# FRA_daughter_v1.net
KiCad netlist of a schematic drawn in EAGLE
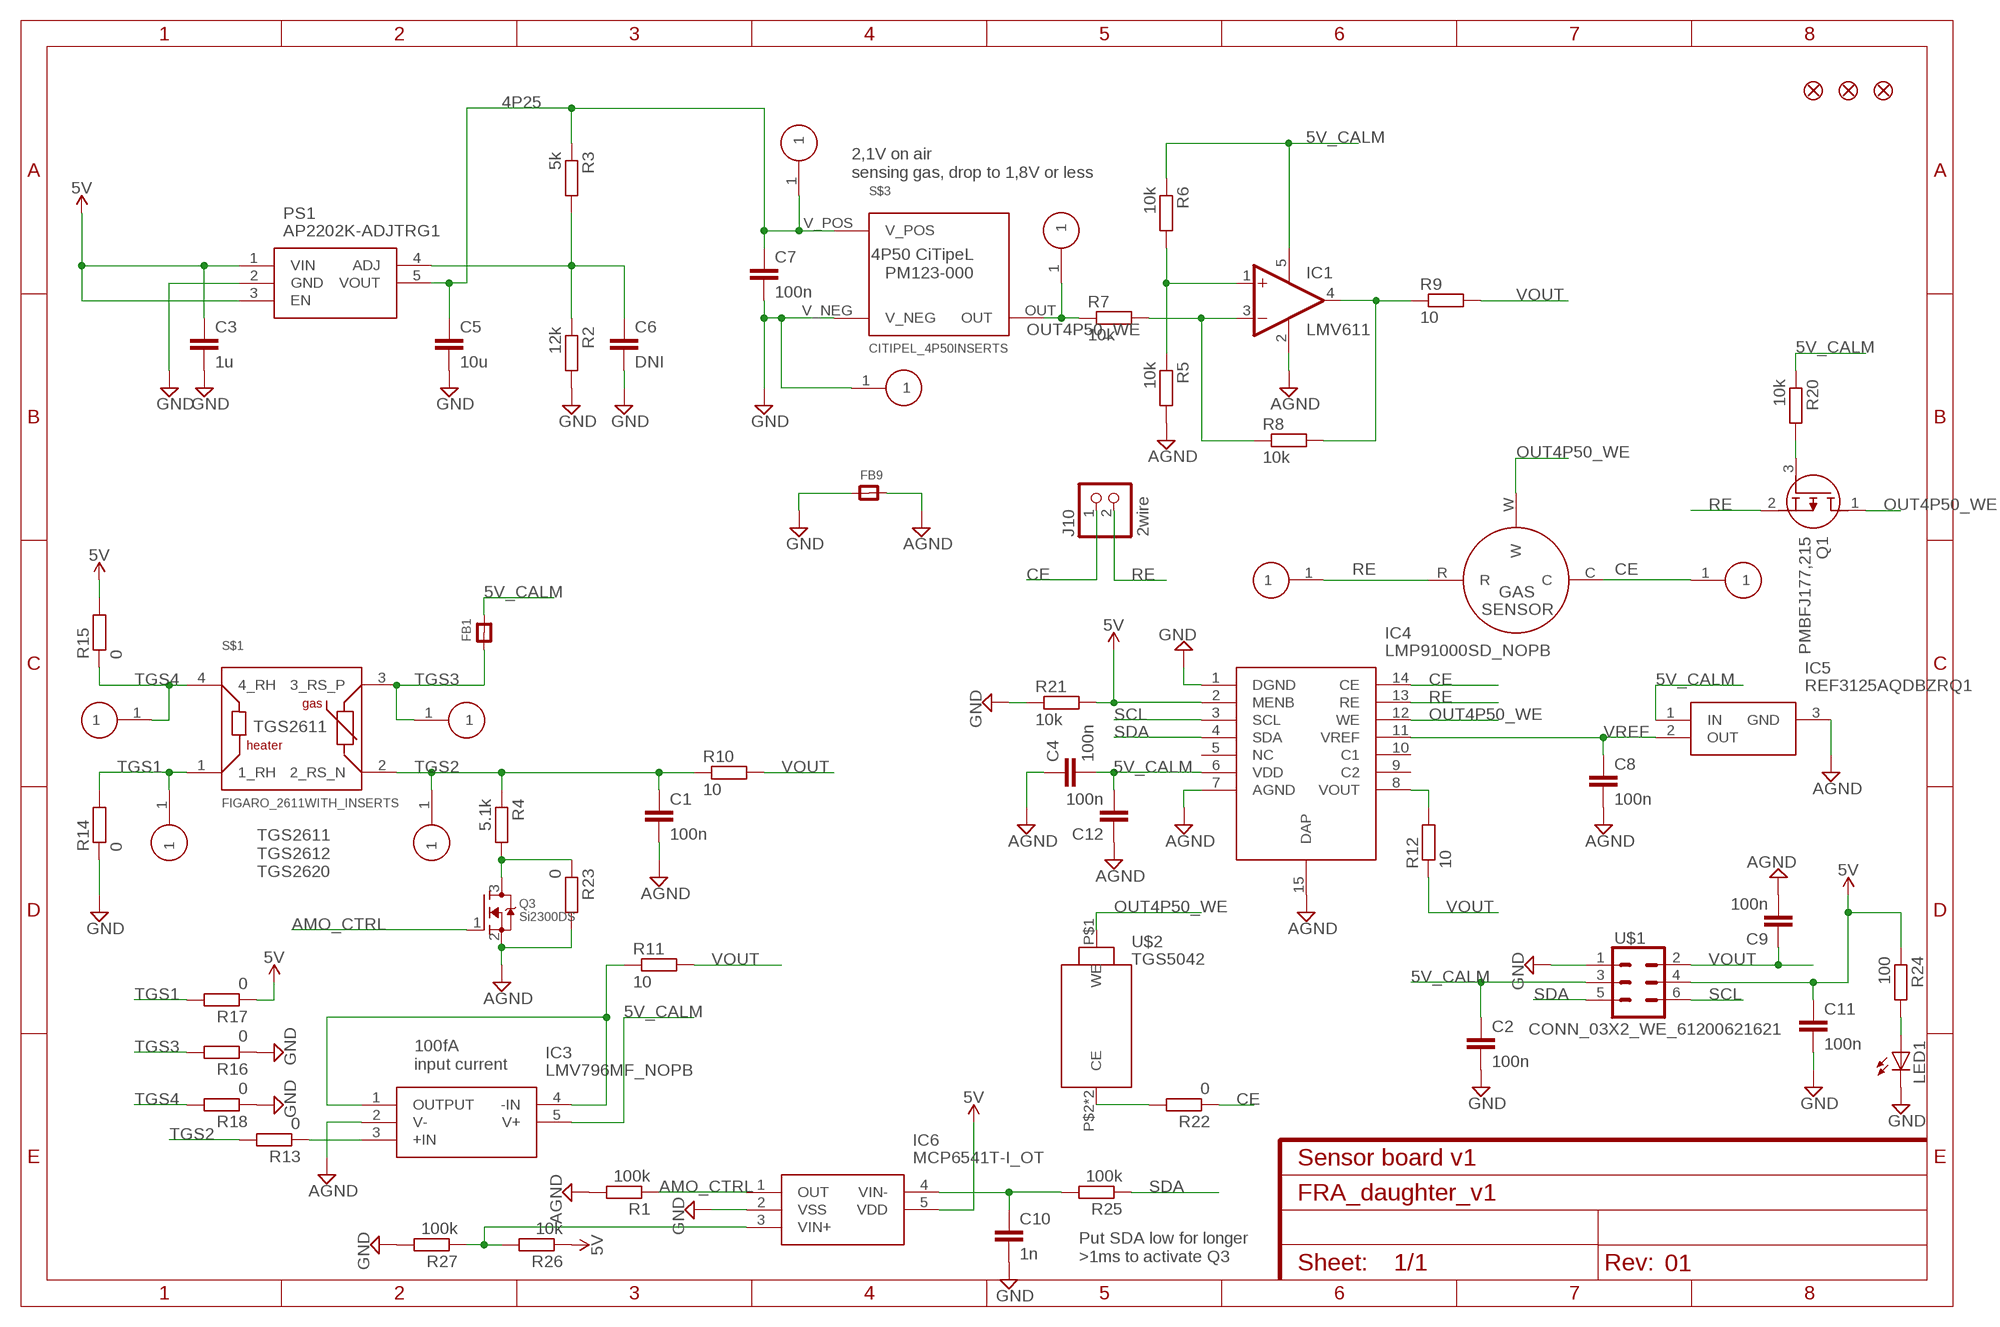
[diagram p0: schematic, sheet 1]

(export (version "E")
  (design (tool "Eeschema 10.0.6"))
  (components
    (comp (ref "C1")
      (value "100n")
      (footprint "eagle-import:C0603K")
      (libsource (lib "eagle-import") (part "C-EUC0603K"))
    )
    (comp (ref "C2")
      (value "100n")
      (footprint "eagle-import:C0603K")
      (libsource (lib "eagle-import") (part "C-EUC0603K"))
    )
    (comp (ref "C3")
      (value "1u")
      (footprint "eagle-import:C0603K")
      (libsource (lib "eagle-import") (part "C-EUC0603K"))
    )
    (comp (ref "C4")
      (value "100n")
      (footprint "eagle-import:C0603K")
      (libsource (lib "eagle-import") (part "C-EUC0603K"))
    )
    (comp (ref "C5")
      (value "10u")
      (footprint "eagle-import:C0603K")
      (libsource (lib "eagle-import") (part "C-EUC0603K"))
    )
    (comp (ref "C6")
      (value "DNI")
      (footprint "eagle-import:C0603K")
      (libsource (lib "eagle-import") (part "C-EUC0603K"))
    )
    (comp (ref "C7")
      (value "100n")
      (footprint "eagle-import:C0603K")
      (libsource (lib "eagle-import") (part "C-EUC0603K"))
    )
    (comp (ref "C8")
      (value "100n")
      (footprint "eagle-import:C0603K")
      (libsource (lib "eagle-import") (part "C-EUC0603K"))
    )
    (comp (ref "C9")
      (value "100n")
      (footprint "eagle-import:C0603K")
      (libsource (lib "eagle-import") (part "C-EUC0603K"))
    )
    (comp (ref "C10")
      (value "1n")
      (footprint "eagle-import:C0603K")
      (libsource (lib "eagle-import") (part "C-EUC0603K"))
    )
    (comp (ref "C11")
      (value "100n")
      (footprint "eagle-import:C0603K")
      (libsource (lib "eagle-import") (part "C-EUC0603K"))
    )
    (comp (ref "C12")
      (value "100n")
      (footprint "eagle-import:C0603K")
      (libsource (lib "eagle-import") (part "C-EUC0603K"))
    )
    (comp (ref "FB1")
      (value "FERRITE")
      (footprint "eagle-import:0603")
      (fields (field (name "PARTNO") "BLM18PG121SN1D"))
      (libsource (lib "eagle-import") (part "FERRITE"))
    )
    (comp (ref "FB9")
      (value "FERRITE")
      (footprint "eagle-import:0603")
      (fields (field (name "PARTNO") "BLM18PG121SN1D"))
      (libsource (lib "eagle-import") (part "FERRITE"))
    )
    (comp (ref "FID1")
      (value "FIDUCIAL\"\"")
      (footprint "eagle-import:FIDUCIAL_1MM")
      (libsource (lib "eagle-import") (part "FIDUCIAL{dblquote}{dblquote}"))
    )
    (comp (ref "FID2")
      (value "FIDUCIAL\"\"")
      (footprint "eagle-import:FIDUCIAL_1MM")
      (libsource (lib "eagle-import") (part "FIDUCIAL{dblquote}{dblquote}"))
    )
    (comp (ref "FID4")
      (value "FIDUCIAL\"\"")
      (footprint "eagle-import:FIDUCIAL_1MM")
      (libsource (lib "eagle-import") (part "FIDUCIAL{dblquote}{dblquote}"))
    )
    (comp (ref "IC1")
      (value "LMV611")
      (footprint "eagle-import:SC70-5L")
      (libsource (lib "eagle-import") (part "OPA333DCK"))
    )
    (comp (ref "IC3")
      (value "LMV796MF_NOPB")
      (footprint "eagle-import:SOT95P280X145-5N")
      (fields
        (field (name "MANUFACTURER_PART_NUMBER") "LMV796MF/NOPB")
        (field (name "MOUSER_PART_NUMBER") "926-LMV796MF/NOPB")
      )
      (libsource (lib "eagle-import") (part "LMV796MF_NOPB"))
    )
    (comp (ref "IC4")
      (value "LMP91000SD_NOPB")
      (footprint "eagle-import:SON50P400X400X80-15N")
      (fields
        (field (name "MANUFACTURER_PART_NUMBER") "LMP91000SD/NOPB")
        (field (name "MOUSER_PART_NUMBER") "926-LMP91000SD/NOPB")
      )
      (libsource (lib "eagle-import") (part "LMP91000SD_NOPB"))
    )
    (comp (ref "IC5")
      (value "REF3125AQDBZRQ1")
      (footprint "eagle-import:SOT95P237X112-3N")
      (fields (field (name "MOUSER_PART_NUMBER") "595-REF3125AQDBZRQ1"))
      (libsource (lib "eagle-import") (part "REF3125AQDBZRQ1"))
    )
    (comp (ref "IC6")
      (value "MCP6541T-I_OT")
      (footprint "eagle-import:SOT95P270X145-5N")
      (fields
        (field (name "MANUFACTURER_PART_NUMBER") "MCP6541T-I/OT")
        (field (name "MOUSER_PART_NUMBER") "579-MCP6541T-I/OT")
      )
      (libsource (lib "eagle-import") (part "MCP6541T-I_OT"))
    )
    (comp (ref "J1")
      (value "INSERT_MM5_06691.5MM")
      (footprint "eagle-import:INSERT_1MM5_9372")
      (libsource (lib "eagle-import") (part "INSERT_MM5_06691.5MM"))
    )
    (comp (ref "J2")
      (value "TGS3")
      (footprint "eagle-import:INSERT_MM5_0669")
      (libsource (lib "eagle-import") (part "INSERT_MM5_0669"))
    )
    (comp (ref "J3")
      (value "TGS2")
      (footprint "eagle-import:INSERT_MM5_0669")
      (libsource (lib "eagle-import") (part "INSERT_MM5_0669"))
    )
    (comp (ref "J4")
      (value "TGS1")
      (footprint "eagle-import:INSERT_MM5_0669")
      (libsource (lib "eagle-import") (part "INSERT_MM5_0669"))
    )
    (comp (ref "J5")
      (value "TGS4")
      (footprint "eagle-import:INSERT_MM5_0669")
      (libsource (lib "eagle-import") (part "INSERT_MM5_0669"))
    )
    (comp (ref "J6")
      (value "INSERT_MM5_06691.5MM")
      (footprint "eagle-import:INSERT_1MM5_9372")
      (libsource (lib "eagle-import") (part "INSERT_MM5_06691.5MM"))
    )
    (comp (ref "J7")
      (value "INSERT_MM5_06691.5MM")
      (footprint "eagle-import:INSERT_1MM5_9372")
      (libsource (lib "eagle-import") (part "INSERT_MM5_06691.5MM"))
    )
    (comp (ref "J8")
      (value "INSERT_MM5_06691.5MM")
      (footprint "eagle-import:INSERT_1MM5_9372")
      (libsource (lib "eagle-import") (part "INSERT_MM5_06691.5MM"))
    )
    (comp (ref "J9")
      (value "INSERT_MM5_06691.5MM")
      (footprint "eagle-import:INSERT_1MM5_9372")
      (libsource (lib "eagle-import") (part "INSERT_MM5_06691.5MM"))
    )
    (comp (ref "J10")
      (value "2wire")
      (footprint "eagle-import:1X02")
      (fields (field (name "PARTNO") "TSW-102-07-G-S"))
      (libsource (lib "eagle-import") (part "PINHD-1X2"))
    )
    (comp (ref "LED1")
      (value "LEDCHIP-LED0603")
      (footprint "eagle-import:CHIP-LED0603")
      (libsource (lib "eagle-import") (part "LEDCHIP-LED0603"))
    )
    (comp (ref "PS1")
      (value "AP2202K-ADJTRG1")
      (footprint "eagle-import:SOT95P280X145-5N")
      (fields (field (name "MOUSER_PART_NUMBER") "621-AP2202K-ADJTRG1"))
      (libsource (lib "eagle-import") (part "AP2202K-ADJTRG1"))
    )
    (comp (ref "Q1")
      (value "PMBFJ177,215")
      (footprint "eagle-import:SOT95P230X110-3N")
      (fields (field (name "MOUSER_PART_NUMBER") "771-PMBFJ177-T/R"))
      (libsource (lib "eagle-import") (part "PMBFJ177,215"))
    )
    (comp (ref "Q3")
      (value "Si2300DS")
      (footprint "eagle-import:SOT23")
      (libsource (lib "eagle-import") (part "MOSFET-NREFLOW"))
    )
    (comp (ref "R1")
      (value "100k")
      (footprint "eagle-import:R0603")
      (libsource (lib "eagle-import") (part "R-EU_R0603"))
    )
    (comp (ref "R2")
      (value "12k")
      (footprint "eagle-import:R0603")
      (libsource (lib "eagle-import") (part "R-EU_R0603"))
    )
    (comp (ref "R3")
      (value "5k")
      (footprint "eagle-import:R0603")
      (libsource (lib "eagle-import") (part "R-EU_R0603"))
    )
    (comp (ref "R4")
      (value "5.1k")
      (footprint "eagle-import:R0603")
      (libsource (lib "eagle-import") (part "R-EU_R0603"))
    )
    (comp (ref "R5")
      (value "10k")
      (footprint "eagle-import:R0603")
      (libsource (lib "eagle-import") (part "R-EU_R0603"))
    )
    (comp (ref "R6")
      (value "10k")
      (footprint "eagle-import:R0603")
      (libsource (lib "eagle-import") (part "R-EU_R0603"))
    )
    (comp (ref "R7")
      (value "10k")
      (footprint "eagle-import:R0603")
      (libsource (lib "eagle-import") (part "R-EU_R0603"))
    )
    (comp (ref "R8")
      (value "10k")
      (footprint "eagle-import:R0603")
      (libsource (lib "eagle-import") (part "R-EU_R0603"))
    )
    (comp (ref "R9")
      (value "10")
      (footprint "eagle-import:R0603")
      (libsource (lib "eagle-import") (part "R-EU_R0603"))
    )
    (comp (ref "R10")
      (value "10")
      (footprint "eagle-import:R0603")
      (libsource (lib "eagle-import") (part "R-EU_R0603"))
    )
    (comp (ref "R11")
      (value "10")
      (footprint "eagle-import:R0603")
      (libsource (lib "eagle-import") (part "R-EU_R0603"))
    )
    (comp (ref "R12")
      (value "10")
      (footprint "eagle-import:R0603")
      (libsource (lib "eagle-import") (part "R-EU_R0603"))
    )
    (comp (ref "R13")
      (value "0")
      (footprint "eagle-import:R0603")
      (libsource (lib "eagle-import") (part "R-EU_R0603"))
    )
    (comp (ref "R14")
      (value "0")
      (footprint "eagle-import:R0603")
      (libsource (lib "eagle-import") (part "R-EU_R0603"))
    )
    (comp (ref "R15")
      (value "0")
      (footprint "eagle-import:R0603")
      (libsource (lib "eagle-import") (part "R-EU_R0603"))
    )
    (comp (ref "R16")
      (value "0")
      (footprint "eagle-import:R0603")
      (libsource (lib "eagle-import") (part "R-EU_R0603"))
    )
    (comp (ref "R17")
      (value "0")
      (footprint "eagle-import:R0603")
      (libsource (lib "eagle-import") (part "R-EU_R0603"))
    )
    (comp (ref "R18")
      (value "0")
      (footprint "eagle-import:R0603")
      (libsource (lib "eagle-import") (part "R-EU_R0603"))
    )
    (comp (ref "R20")
      (value "10k")
      (footprint "eagle-import:R0603")
      (libsource (lib "eagle-import") (part "R-EU_R0603"))
    )
    (comp (ref "R21")
      (value "10k")
      (footprint "eagle-import:R0603")
      (libsource (lib "eagle-import") (part "R-EU_R0603"))
    )
    (comp (ref "R22")
      (value "0")
      (footprint "eagle-import:R0603")
      (libsource (lib "eagle-import") (part "R-EU_R0603"))
    )
    (comp (ref "R23")
      (value "0")
      (footprint "eagle-import:R0603")
      (libsource (lib "eagle-import") (part "R-EU_R0603"))
    )
    (comp (ref "R24")
      (value "100")
      (footprint "eagle-import:R0603")
      (libsource (lib "eagle-import") (part "R-EU_R0603"))
    )
    (comp (ref "R25")
      (value "100k")
      (footprint "eagle-import:R0603")
      (libsource (lib "eagle-import") (part "R-EU_R0603"))
    )
    (comp (ref "R26")
      (value "10k")
      (footprint "eagle-import:R0603")
      (libsource (lib "eagle-import") (part "R-EU_R0603"))
    )
    (comp (ref "R27")
      (value "100k")
      (footprint "eagle-import:R0603")
      (libsource (lib "eagle-import") (part "R-EU_R0603"))
    )
    (comp (ref "S$1")
      (value "FIGARO_2611WITH_INSERTS")
      (footprint "eagle-import:TH4_TGS2611_INSERTS")
      (libsource (lib "eagle-import") (part "FIGARO_2611WITH_INSERTS"))
    )
    (comp (ref "S$3")
      (value "CITIPEL_4P50INSERTS")
      (footprint "eagle-import:TH3_4P50_INSERTS")
      (libsource (lib "eagle-import") (part "CITIPEL_4P50INSERTS"))
    )
    (comp (ref "U$1")
      (value "CONN_03X2_WE_61200621621")
      (footprint "eagle-import:WE_61200621621")
      (libsource (lib "eagle-import") (part "CONN_03X2_WE_61200621621"))
    )
    (comp (ref "U$2")
      (value "TGS5042")
      (footprint "eagle-import:TGS5042")
      (libsource (lib "eagle-import") (part "TGS5042"))
    )
    (comp (ref "X1")
      (value "3-ELECTRODE-GAS-SENSORINS")
      (footprint "eagle-import:3-ELECTRODE_INSETRS")
      (libsource (lib "eagle-import") (part "3-ELECTRODE-GAS-SENSORINS"))
    )
  )
  (nets
    (net (code "1") (name "/4P25") (class "Default")
      (node (ref "C5") (pin "1") (pinfunction "1_1") (pintype "passive"))
      (node (ref "C7") (pin "1") (pinfunction "1_1") (pintype "passive"))
      (node (ref "J6") (pin "1") (pinfunction "1_1") (pintype "bidirectional"))
      (node (ref "PS1") (pin "5") (pinfunction "VOUT_5") (pintype "power_in"))
      (node (ref "R3") (pin "1") (pinfunction "1_1") (pintype "passive"))
      (node (ref "S$3") (pin "V_POS") (pinfunction "V_POS_V_POS") (pintype "power_in"))
    )
    (net (code "2") (name "/5V_CALM") (class "Default")
      (node (ref "C12") (pin "2") (pinfunction "2_2") (pintype "passive"))
      (node (ref "C2") (pin "1") (pinfunction "1_1") (pintype "passive"))
      (node (ref "C4") (pin "2") (pinfunction "2_2") (pintype "passive"))
      (node (ref "FB1") (pin "2") (pinfunction "P$2_2") (pintype "passive"))
      (node (ref "IC1") (pin "5") (pinfunction "V+_5") (pintype "power_in"))
      (node (ref "IC3") (pin "5") (pinfunction "V+_5") (pintype "bidirectional"))
      (node (ref "IC4") (pin "6") (pinfunction "VDD_6") (pintype "power_in"))
      (node (ref "IC5") (pin "1") (pinfunction "IN_1") (pintype "bidirectional"))
      (node (ref "R20") (pin "1") (pinfunction "1_1") (pintype "passive"))
      (node (ref "R6") (pin "1") (pinfunction "1_1") (pintype "passive"))
      (node (ref "U$1") (pin "3") (pinfunction "3_3") (pintype "bidirectional"))
    )
    (net (code "3") (name "/AMO_CTRL") (class "Default")
      (node (ref "IC6") (pin "1") (pinfunction "OUT_1") (pintype "output"))
      (node (ref "Q3") (pin "1") (pinfunction "G_1") (pintype "bidirectional"))
      (node (ref "R1") (pin "1") (pinfunction "1_1") (pintype "passive"))
    )
    (net (code "4") (name "/CE") (class "Default")
      (node (ref "IC4") (pin "14") (pinfunction "CE_14") (pintype "input"))
      (node (ref "J10") (pin "1") (pinfunction "1_1") (pintype "passive"))
      (node (ref "J9") (pin "1") (pinfunction "1_1") (pintype "bidirectional"))
      (node (ref "R22") (pin "1") (pinfunction "1_1") (pintype "passive"))
      (node (ref "X1") (pin "C") (pinfunction "C_C") (pintype "bidirectional"))
    )
    (net (code "5") (name "/OUT4P50_WE") (class "Default")
      (node (ref "IC4") (pin "12") (pinfunction "WE_12") (pintype "input"))
      (node (ref "J7") (pin "1") (pinfunction "1_1") (pintype "bidirectional"))
      (node (ref "Q1") (pin "1") (pinfunction "D_1") (pintype "bidirectional"))
      (node (ref "R7") (pin "1") (pinfunction "1_1") (pintype "passive"))
      (node (ref "S$3") (pin "OUT") (pinfunction "OUT_OUT") (pintype "bidirectional"))
      (node (ref "U$2") (pin "P$1") (pinfunction "WE_P$1") (pintype "bidirectional"))
      (node (ref "X1") (pin "W") (pinfunction "W_W") (pintype "bidirectional"))
    )
    (net (code "6") (name "/RE") (class "Default")
      (node (ref "IC4") (pin "13") (pinfunction "RE_13") (pintype "input"))
      (node (ref "J10") (pin "2") (pinfunction "2_2") (pintype "passive"))
      (node (ref "J8") (pin "1") (pinfunction "1_1") (pintype "bidirectional"))
      (node (ref "Q1") (pin "2") (pinfunction "S_2") (pintype "bidirectional"))
      (node (ref "X1") (pin "R") (pinfunction "R_R") (pintype "bidirectional"))
    )
    (net (code "7") (name "/SCL") (class "Default")
      (node (ref "IC4") (pin "3") (pinfunction "SCL_3") (pintype "input"))
      (node (ref "U$1") (pin "6") (pinfunction "6_6") (pintype "bidirectional"))
    )
    (net (code "8") (name "/SDA") (class "Default")
      (node (ref "IC4") (pin "4") (pinfunction "SDA_4") (pintype "bidirectional"))
      (node (ref "R25") (pin "1") (pinfunction "1_1") (pintype "passive"))
      (node (ref "U$1") (pin "5") (pinfunction "5_5") (pintype "bidirectional"))
    )
    (net (code "9") (name "/TGS1") (class "Default")
      (node (ref "J4") (pin "1") (pinfunction "1_1") (pintype "bidirectional"))
      (node (ref "R14") (pin "2") (pinfunction "2_2") (pintype "passive"))
      (node (ref "R17") (pin "2") (pinfunction "2_2") (pintype "passive"))
      (node (ref "S$1") (pin "1") (pinfunction "1_RH_1") (pintype "bidirectional"))
    )
    (net (code "10") (name "/TGS2") (class "Default")
      (node (ref "C1") (pin "1") (pinfunction "1_1") (pintype "passive"))
      (node (ref "J3") (pin "1") (pinfunction "1_1") (pintype "bidirectional"))
      (node (ref "R10") (pin "1") (pinfunction "1_1") (pintype "passive"))
      (node (ref "R13") (pin "2") (pinfunction "2_2") (pintype "passive"))
      (node (ref "R4") (pin "1") (pinfunction "1_1") (pintype "passive"))
      (node (ref "S$1") (pin "2") (pinfunction "2_RS_N_2") (pintype "bidirectional"))
    )
    (net (code "11") (name "/TGS3") (class "Default")
      (node (ref "FB1") (pin "1") (pinfunction "P$1_1") (pintype "passive"))
      (node (ref "J2") (pin "1") (pinfunction "1_1") (pintype "bidirectional"))
      (node (ref "R16") (pin "2") (pinfunction "2_2") (pintype "passive"))
      (node (ref "S$1") (pin "3") (pinfunction "3_RS_P_3") (pintype "bidirectional"))
    )
    (net (code "12") (name "/TGS4") (class "Default")
      (node (ref "J5") (pin "1") (pinfunction "1_1") (pintype "bidirectional"))
      (node (ref "R15") (pin "1") (pinfunction "1_1") (pintype "passive"))
      (node (ref "R18") (pin "2") (pinfunction "2_2") (pintype "passive"))
      (node (ref "S$1") (pin "4") (pinfunction "4_RH_4") (pintype "bidirectional"))
    )
    (net (code "13") (name "/VOUT") (class "Default")
      (node (ref "C9") (pin "1") (pinfunction "1_1") (pintype "passive"))
      (node (ref "R10") (pin "2") (pinfunction "2_2") (pintype "passive"))
      (node (ref "R11") (pin "2") (pinfunction "2_2") (pintype "passive"))
      (node (ref "R12") (pin "1") (pinfunction "1_1") (pintype "passive"))
      (node (ref "R9") (pin "2") (pinfunction "2_2") (pintype "passive"))
      (node (ref "U$1") (pin "2") (pinfunction "2_2") (pintype "bidirectional"))
    )
    (net (code "14") (name "/VREF") (class "Default")
      (node (ref "C8") (pin "1") (pinfunction "1_1") (pintype "passive"))
      (node (ref "IC4") (pin "11") (pinfunction "VREF_11") (pintype "input"))
      (node (ref "IC5") (pin "2") (pinfunction "OUT_2") (pintype "bidirectional"))
    )
    (net (code "15") (name "5V") (class "Default")
      (node (ref "C11") (pin "1") (pinfunction "1_1") (pintype "passive"))
      (node (ref "C3") (pin "1") (pinfunction "1_1") (pintype "passive"))
      (node (ref "IC4") (pin "2") (pinfunction "MENB_2") (pintype "input"))
      (node (ref "IC6") (pin "5") (pinfunction "VDD_5") (pintype "power_in"))
      (node (ref "PS1") (pin "1") (pinfunction "VIN_1") (pintype "power_in"))
      (node (ref "PS1") (pin "3") (pinfunction "EN_3") (pintype "input"))
      (node (ref "R15") (pin "2") (pinfunction "2_2") (pintype "passive"))
      (node (ref "R17") (pin "1") (pinfunction "1_1") (pintype "passive"))
      (node (ref "R21") (pin "2") (pinfunction "2_2") (pintype "passive"))
      (node (ref "R24") (pin "1") (pinfunction "1_1") (pintype "passive"))
      (node (ref "R26") (pin "1") (pinfunction "1_1") (pintype "passive"))
      (node (ref "U$1") (pin "4") (pinfunction "4_4") (pintype "bidirectional"))
    )
    (net (code "16") (name "AGND") (class "Default")
      (node (ref "C1") (pin "2") (pinfunction "2_2") (pintype "passive"))
      (node (ref "C12") (pin "1") (pinfunction "1_1") (pintype "passive"))
      (node (ref "C4") (pin "1") (pinfunction "1_1") (pintype "passive"))
      (node (ref "C8") (pin "2") (pinfunction "2_2") (pintype "passive"))
      (node (ref "C9") (pin "2") (pinfunction "2_2") (pintype "passive"))
      (node (ref "FB9") (pin "2") (pinfunction "P$2_2") (pintype "passive"))
      (node (ref "IC1") (pin "2") (pinfunction "V-_2") (pintype "power_in"))
      (node (ref "IC3") (pin "2") (pinfunction "V-_2") (pintype "bidirectional"))
      (node (ref "IC4") (pin "15") (pinfunction "DAP_15") (pintype "power_in"))
      (node (ref "IC4") (pin "7") (pinfunction "AGND_7") (pintype "power_in"))
      (node (ref "IC5") (pin "3") (pinfunction "GND_3") (pintype "bidirectional"))
      (node (ref "Q3") (pin "2") (pinfunction "S_2") (pintype "bidirectional"))
      (node (ref "R1") (pin "2") (pinfunction "2_2") (pintype "passive"))
      (node (ref "R23") (pin "2") (pinfunction "2_2") (pintype "passive"))
      (node (ref "R5") (pin "2") (pinfunction "2_2") (pintype "passive"))
    )
    (net (code "17") (name "GND") (class "Default")
      (node (ref "C10") (pin "2") (pinfunction "2_2") (pintype "passive"))
      (node (ref "C11") (pin "2") (pinfunction "2_2") (pintype "passive"))
      (node (ref "C2") (pin "2") (pinfunction "2_2") (pintype "passive"))
      (node (ref "C3") (pin "2") (pinfunction "2_2") (pintype "passive"))
      (node (ref "C5") (pin "2") (pinfunction "2_2") (pintype "passive"))
      (node (ref "C6") (pin "2") (pinfunction "2_2") (pintype "passive"))
      (node (ref "C7") (pin "2") (pinfunction "2_2") (pintype "passive"))
      (node (ref "FB9") (pin "1") (pinfunction "P$1_1") (pintype "passive"))
      (node (ref "IC4") (pin "1") (pinfunction "DGND_1") (pintype "power_in"))
      (node (ref "IC6") (pin "2") (pinfunction "VSS_2") (pintype "power_in"))
      (node (ref "J1") (pin "1") (pinfunction "1_1") (pintype "bidirectional"))
      (node (ref "LED1") (pin "C") (pinfunction "C_C") (pintype "passive"))
      (node (ref "PS1") (pin "2") (pinfunction "GND_2") (pintype "power_in"))
      (node (ref "R14") (pin "1") (pinfunction "1_1") (pintype "passive"))
      (node (ref "R16") (pin "1") (pinfunction "1_1") (pintype "passive"))
      (node (ref "R18") (pin "1") (pinfunction "1_1") (pintype "passive"))
      (node (ref "R2") (pin "2") (pinfunction "2_2") (pintype "passive"))
      (node (ref "R21") (pin "1") (pinfunction "1_1") (pintype "passive"))
      (node (ref "R27") (pin "2") (pinfunction "2_2") (pintype "passive"))
      (node (ref "S$3") (pin "V_NEG") (pinfunction "V_NEG_V_NEG") (pintype "power_in"))
      (node (ref "U$1") (pin "1") (pinfunction "1_1") (pintype "bidirectional"))
    )
    (net (code "18") (name "Net-(IC1-+IN)") (class "Default")
      (node (ref "IC1") (pin "1") (pinfunction "+IN_1") (pintype "input"))
      (node (ref "R5") (pin "1") (pinfunction "1_1") (pintype "passive"))
      (node (ref "R6") (pin "2") (pinfunction "2_2") (pintype "passive"))
    )
    (net (code "19") (name "Net-(IC1--IN)") (class "Default")
      (node (ref "IC1") (pin "3") (pinfunction "-IN_3") (pintype "input"))
      (node (ref "R7") (pin "2") (pinfunction "2_2") (pintype "passive"))
      (node (ref "R8") (pin "1") (pinfunction "1_1") (pintype "passive"))
    )
    (net (code "20") (name "Net-(IC1-OUT)") (class "Default")
      (node (ref "IC1") (pin "4") (pinfunction "OUT_4") (pintype "output"))
      (node (ref "R8") (pin "2") (pinfunction "2_2") (pintype "passive"))
      (node (ref "R9") (pin "1") (pinfunction "1_1") (pintype "passive"))
    )
    (net (code "21") (name "Net-(IC3-+IN)") (class "Default")
      (node (ref "IC3") (pin "3") (pinfunction "+IN_3") (pintype "input"))
      (node (ref "R13") (pin "1") (pinfunction "1_1") (pintype "passive"))
    )
    (net (code "22") (name "Net-(IC3--IN)") (class "Default")
      (node (ref "IC3") (pin "1") (pinfunction "OUTPUT_1") (pintype "output"))
      (node (ref "IC3") (pin "4") (pinfunction "-IN_4") (pintype "input"))
      (node (ref "R11") (pin "1") (pinfunction "1_1") (pintype "passive"))
    )
    (net (code "23") (name "Net-(IC4-VOUT)") (class "Default")
      (node (ref "IC4") (pin "8") (pinfunction "VOUT_8") (pintype "output"))
      (node (ref "R12") (pin "2") (pinfunction "2_2") (pintype "passive"))
    )
    (net (code "24") (name "Net-(IC6-VIN+)") (class "Default")
      (node (ref "IC6") (pin "3") (pinfunction "VIN+_3") (pintype "input"))
      (node (ref "R26") (pin "2") (pinfunction "2_2") (pintype "passive"))
      (node (ref "R27") (pin "1") (pinfunction "1_1") (pintype "passive"))
    )
    (net (code "25") (name "Net-(IC6-VIN-)") (class "Default")
      (node (ref "C10") (pin "1") (pinfunction "1_1") (pintype "passive"))
      (node (ref "IC6") (pin "4") (pinfunction "VIN-_4") (pintype "input"))
      (node (ref "R25") (pin "2") (pinfunction "2_2") (pintype "passive"))
    )
    (net (code "26") (name "Net-(LED1-PadA)") (class "Default")
      (node (ref "LED1") (pin "A") (pinfunction "A_A") (pintype "passive"))
      (node (ref "R24") (pin "2") (pinfunction "2_2") (pintype "passive"))
    )
    (net (code "27") (name "Net-(PS1-ADJ)") (class "Default")
      (node (ref "C6") (pin "1") (pinfunction "1_1") (pintype "passive"))
      (node (ref "PS1") (pin "4") (pinfunction "ADJ_4") (pintype "bidirectional"))
      (node (ref "R2") (pin "1") (pinfunction "1_1") (pintype "passive"))
      (node (ref "R3") (pin "2") (pinfunction "2_2") (pintype "passive"))
    )
    (net (code "28") (name "Net-(Q1-G)") (class "Default")
      (node (ref "Q1") (pin "3") (pinfunction "G_3") (pintype "bidirectional"))
      (node (ref "R20") (pin "2") (pinfunction "2_2") (pintype "passive"))
    )
    (net (code "29") (name "Net-(Q3-D)") (class "Default")
      (node (ref "Q3") (pin "3") (pinfunction "D_3") (pintype "bidirectional"))
      (node (ref "R23") (pin "1") (pinfunction "1_1") (pintype "passive"))
      (node (ref "R4") (pin "2") (pinfunction "2_2") (pintype "passive"))
    )
    (net (code "30") (name "Net-(R22-Pad2)") (class "Default")
      (node (ref "R22") (pin "2") (pinfunction "2_2") (pintype "passive"))
      (node (ref "U$2") (pin "P$2") (pinfunction "CE_P$2") (pintype "bidirectional"))
      (node (ref "U$2") (pin "P$3") (pinfunction "CE_P$3") (pintype "bidirectional"))
    )
    (net (code "31") (name "unconnected-(IC4-C1-Pad10)") (class "Default")
      (node (ref "IC4") (pin "10") (pinfunction "C1_10") (pintype "bidirectional"))
    )
    (net (code "32") (name "unconnected-(IC4-C2-Pad9)") (class "Default")
      (node (ref "IC4") (pin "9") (pinfunction "C2_9") (pintype "bidirectional"))
    )
    (net (code "33") (name "unconnected-(IC4-NC-Pad5)") (class "Default")
      (node (ref "IC4") (pin "5") (pinfunction "NC_5") (pintype "no_connect"))
    )
  )
)
